# Sheet1.net
KiCad netlist of a schematic drawn in Altium Designer
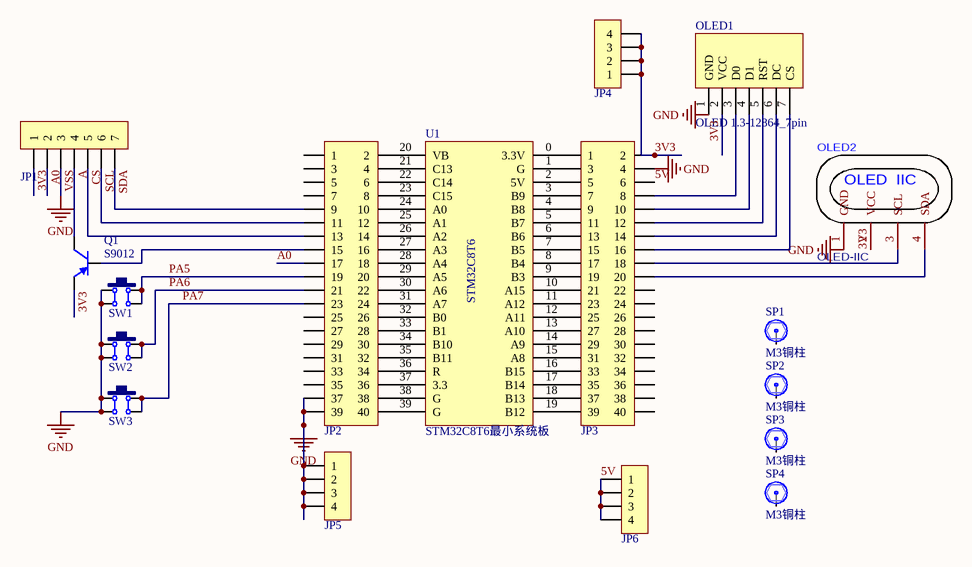
[diagram p0: Sheet1.SchDoc]

(export (version "E")
  (design (tool "Eeschema 10.0.6"))
  (components
    (comp (ref "JP1")
      (value "HDR-1X7")
      (footprint "XH2.54-WI-7P")
      (description "7P接插件  2.54")
      (fields (field (name "版权归属") "源创客"))
      (libsource (lib "MyLibra_Myself") (part "Header 7  2.54"))
    )
    (comp (ref "JP2")
      (value "Header 2X11")
      (footprint "HDR2.54-LI-2x20P")
      (description "20*2P接插件  2.54")
      (fields (field (name "版权归属") "源创客"))
      (libsource (lib "MyLibra_Myself") (part "Header 20X2  2.54"))
    )
    (comp (ref "JP3")
      (value "Header 2X11")
      (footprint "HDR2.54-LI-2x20P")
      (description "20*2P接插件  2.54")
      (fields (field (name "版权归属") "源创客"))
      (libsource (lib "MyLibra_Myself") (part "Header 20X2  2.54"))
    )
    (comp (ref "JP4")
      (value "HDR-1X4")
      (footprint "HDR2.54-M-LI-4P")
      (description "4P接插件  2.54")
      (fields (field (name "版权归属") "源创客"))
      (libsource (lib "") (part "Header 4  2.54_1"))
    )
    (comp (ref "JP5")
      (value "HDR-1X4")
      (footprint "HDR2.54-LI-4P")
      (description "4P接插件  2.54")
      (fields (field (name "版权归属") "源创客"))
      (libsource (lib "MyLibra_Myself") (part "Header 4  2.54"))
    )
    (comp (ref "JP6")
      (value "HDR-1X4")
      (footprint "HDR2.54-LI-4P")
      (description "4P接插件  2.54")
      (fields (field (name "版权归属") "源创客"))
      (libsource (lib "MyLibra_Myself") (part "Header 4  2.54"))
    )
    (comp (ref "OLED1")
      (value "OLED 1.3-12864_7pin")
      (footprint "1.3-SPI-OLED")
      (description "12864 点阵屏")
      (fields (field (name "版权归属") "源创客"))
      (libsource (lib "MyLibra_Myself") (part "OLED-SPI"))
    )
    (comp (ref "OLED2")
      (value "OLED-IIC")
      (footprint "0.96-IIC-OLED")
      (description "OLED 0.96寸 1.3寸 IIC显示屏")
      (libsource (lib "MyLibra_Myself") (part "OLED-IIC"))
    )
    (comp (ref "Q1")
      (value "S9012")
      (footprint "TO92A")
      (description "低频放大-PNP型")
      (fields (field (name "版权归属") "源创客"))
      (libsource (lib "综合库") (part "9012-DIP"))
    )
    (comp (ref "SP1")
      (value "M3铜柱")
      (footprint "M3x4_L")
      (description "铜柱")
      (fields (field (name "版权归属") "源创客"))
      (libsource (lib "综合库") (part "铜柱小焊盘"))
    )
    (comp (ref "SP2")
      (value "M3铜柱")
      (footprint "M3x4_L")
      (description "铜柱")
      (fields (field (name "版权归属") "源创客"))
      (libsource (lib "综合库") (part "铜柱小焊盘"))
    )
    (comp (ref "SP3")
      (value "M3铜柱")
      (footprint "M3x4_L")
      (description "铜柱")
      (fields (field (name "版权归属") "源创客"))
      (libsource (lib "综合库") (part "铜柱小焊盘"))
    )
    (comp (ref "SP4")
      (value "M3铜柱")
      (footprint "M3x4_L")
      (description "铜柱")
      (fields (field (name "版权归属") "源创客"))
      (libsource (lib "综合库") (part "铜柱小焊盘"))
    )
    (comp (ref "SW1")
      (value "12x12x5")
      (footprint "TSW DIP-12*12*4.3")
      (description "直插12x12轻触开关")
      (fields (field (name "版权归属") "源创客"))
      (libsource (lib "MyLibra_Myself") (part "TSW DIP-12x12"))
    )
    (comp (ref "SW2")
      (value "12x12x5")
      (footprint "TSW DIP-12*12*4.3")
      (description "直插12x12轻触开关")
      (fields (field (name "版权归属") "源创客"))
      (libsource (lib "MyLibra_Myself") (part "TSW DIP-12x12"))
    )
    (comp (ref "SW3")
      (value "12x12x5")
      (footprint "TSW DIP-12*12*4.3")
      (description "直插12x12轻触开关")
      (fields (field (name "版权归属") "源创客"))
      (libsource (lib "MyLibra_Myself") (part "TSW DIP-12x12"))
    )
    (comp (ref "U1")
      (value "STM32C8T6最小系统板")
      (footprint "STM32C8T6")
      (libsource (lib "MyLibra_Myself") (part "STM32C8T6最小系统板"))
    )
  )
  (nets
    (net (code "1") (name "/3V3") (class "Default")
      (node (ref "JP1") (pin "1") (pinfunction "1_1") (pintype "passive"))
      (node (ref "JP3") (pin "2") (pinfunction "2_2") (pintype "passive"))
      (node (ref "JP4") (pin "1") (pinfunction "1_1") (pintype "passive"))
      (node (ref "JP4") (pin "2") (pinfunction "2_2") (pintype "passive"))
      (node (ref "JP4") (pin "3") (pinfunction "3_3") (pintype "passive"))
      (node (ref "JP4") (pin "4") (pinfunction "4_4") (pintype "passive"))
      (node (ref "OLED1") (pin "2") (pinfunction "VCC_2") (pintype "passive"))
      (node (ref "OLED2") (pin "2") (pinfunction "VCC_2") (pintype "passive"))
      (node (ref "Q1") (pin "1") (pinfunction "E_1") (pintype "passive"))
    )
    (net (code "2") (name "/5V") (class "Default")
      (node (ref "JP3") (pin "6") (pinfunction "6_6") (pintype "passive"))
      (node (ref "JP6") (pin "1") (pinfunction "1_1") (pintype "passive"))
      (node (ref "JP6") (pin "2") (pinfunction "2_2") (pintype "passive"))
      (node (ref "JP6") (pin "3") (pinfunction "3_3") (pintype "passive"))
      (node (ref "JP6") (pin "4") (pinfunction "4_4") (pintype "passive"))
    )
    (net (code "3") (name "/A") (class "Default")
      (node (ref "JP1") (pin "4") (pinfunction "4_4") (pintype "passive"))
      (node (ref "Q1") (pin "3") (pinfunction "C_3") (pintype "passive"))
    )
    (net (code "4") (name "/A0") (class "Default")
      (node (ref "JP1") (pin "2") (pinfunction "2_2") (pintype "passive"))
      (node (ref "JP2") (pin "17") (pinfunction "17_17") (pintype "passive"))
    )
    (net (code "5") (name "/CS") (class "Default")
      (node (ref "JP1") (pin "5") (pinfunction "5_5") (pintype "passive"))
      (node (ref "JP2") (pin "13") (pinfunction "13_13") (pintype "passive"))
    )
    (net (code "6") (name "/PA5") (class "Default")
      (node (ref "JP2") (pin "19") (pinfunction "19_19") (pintype "passive"))
      (node (ref "SW1") (pin "2") (pinfunction "2_2") (pintype "passive"))
      (node (ref "SW1") (pin "3") (pinfunction "3_3") (pintype "passive"))
    )
    (net (code "7") (name "/PA6") (class "Default")
      (node (ref "JP2") (pin "21") (pinfunction "21_21") (pintype "passive"))
      (node (ref "SW2") (pin "2") (pinfunction "2_2") (pintype "passive"))
      (node (ref "SW2") (pin "3") (pinfunction "3_3") (pintype "passive"))
    )
    (net (code "8") (name "/PA7") (class "Default")
      (node (ref "JP2") (pin "23") (pinfunction "23_23") (pintype "passive"))
      (node (ref "SW3") (pin "2") (pinfunction "2_2") (pintype "passive"))
      (node (ref "SW3") (pin "3") (pinfunction "3_3") (pintype "passive"))
    )
    (net (code "9") (name "/SCL") (class "Default")
      (node (ref "JP1") (pin "6") (pinfunction "6_6") (pintype "passive"))
      (node (ref "JP2") (pin "11") (pinfunction "11_11") (pintype "passive"))
    )
    (net (code "10") (name "/SDA") (class "Default")
      (node (ref "JP1") (pin "7") (pinfunction "7_7") (pintype "passive"))
      (node (ref "JP2") (pin "9") (pinfunction "9_9") (pintype "passive"))
    )
    (net (code "11") (name "GND") (class "Default")
      (node (ref "JP1") (pin "3") (pinfunction "3_3") (pintype "passive"))
      (node (ref "JP2") (pin "37") (pinfunction "37_37") (pintype "passive"))
      (node (ref "JP2") (pin "39") (pinfunction "39_39") (pintype "passive"))
      (node (ref "JP3") (pin "4") (pinfunction "4_4") (pintype "passive"))
      (node (ref "JP5") (pin "1") (pinfunction "1_1") (pintype "passive"))
      (node (ref "JP5") (pin "2") (pinfunction "2_2") (pintype "passive"))
      (node (ref "JP5") (pin "3") (pinfunction "3_3") (pintype "passive"))
      (node (ref "JP5") (pin "4") (pinfunction "4_4") (pintype "passive"))
      (node (ref "OLED1") (pin "1") (pinfunction "GND_1") (pintype "passive"))
      (node (ref "OLED2") (pin "1") (pinfunction "GND_1") (pintype "passive"))
      (node (ref "SW1") (pin "1") (pinfunction "1_1") (pintype "passive"))
      (node (ref "SW1") (pin "4") (pinfunction "4_4") (pintype "passive"))
      (node (ref "SW2") (pin "1") (pinfunction "1_1") (pintype "passive"))
      (node (ref "SW2") (pin "4") (pinfunction "4_4") (pintype "passive"))
      (node (ref "SW3") (pin "1") (pinfunction "1_1") (pintype "passive"))
      (node (ref "SW3") (pin "4") (pinfunction "4_4") (pintype "passive"))
    )
    (net (code "12") (name "Net-(JP2-Pad38)") (class "Default")
      (node (ref "JP2") (pin "38") (pinfunction "38_38") (pintype "passive"))
      (node (ref "U1") (pin "38") (pinfunction "G_38") (pintype "passive"))
    )
    (net (code "13") (name "Net-(JP2-Pad40)") (class "Default")
      (node (ref "JP2") (pin "40") (pinfunction "40_40") (pintype "passive"))
      (node (ref "U1") (pin "39") (pinfunction "G_39") (pintype "passive"))
    )
    (net (code "14") (name "Net-(JP3-Pad3)") (class "Default")
      (node (ref "JP3") (pin "3") (pinfunction "3_3") (pintype "passive"))
      (node (ref "U1") (pin "1") (pinfunction "G_1") (pintype "passive"))
    )
    (net (code "15") (name "Net-(OLED1-CS)") (class "Default")
      (node (ref "JP3") (pin "16") (pinfunction "16_16") (pintype "passive"))
      (node (ref "OLED1") (pin "7") (pinfunction "CS_7") (pintype "passive"))
    )
    (net (code "16") (name "Net-(OLED1-D0)") (class "Default")
      (node (ref "JP3") (pin "8") (pinfunction "8_8") (pintype "passive"))
      (node (ref "OLED1") (pin "3") (pinfunction "D0_3") (pintype "passive"))
    )
    (net (code "17") (name "Net-(OLED1-D1)") (class "Default")
      (node (ref "JP3") (pin "10") (pinfunction "10_10") (pintype "passive"))
      (node (ref "OLED1") (pin "4") (pinfunction "D1_4") (pintype "passive"))
    )
    (net (code "18") (name "Net-(OLED1-DC)") (class "Default")
      (node (ref "JP3") (pin "14") (pinfunction "14_14") (pintype "passive"))
      (node (ref "OLED1") (pin "6") (pinfunction "DC_6") (pintype "passive"))
    )
    (net (code "19") (name "Net-(OLED1-RST)") (class "Default")
      (node (ref "JP3") (pin "12") (pinfunction "12_12") (pintype "passive"))
      (node (ref "OLED1") (pin "5") (pinfunction "RST_5") (pintype "passive"))
    )
    (net (code "20") (name "Net-(OLED2-SCL)") (class "Default")
      (node (ref "JP3") (pin "18") (pinfunction "18_18") (pintype "passive"))
      (node (ref "OLED2") (pin "3") (pinfunction "SCL_3") (pintype "passive"))
    )
    (net (code "21") (name "Net-(OLED2-SDA)") (class "Default")
      (node (ref "JP3") (pin "20") (pinfunction "20_20") (pintype "passive"))
      (node (ref "OLED2") (pin "4") (pinfunction "SDA_4") (pintype "passive"))
    )
    (net (code "22") (name "Net-(Q1-B)") (class "Default")
      (node (ref "JP2") (pin "15") (pinfunction "15_15") (pintype "passive"))
      (node (ref "Q1") (pin "2") (pinfunction "B_2") (pintype "passive"))
    )
    (net (code "23") (name "Net-(U1-3.3)") (class "Default")
      (node (ref "JP2") (pin "36") (pinfunction "36_36") (pintype "passive"))
      (node (ref "U1") (pin "37") (pinfunction "3.3_37") (pintype "passive"))
    )
    (net (code "24") (name "Net-(U1-3.3V)") (class "Default")
      (node (ref "JP3") (pin "1") (pinfunction "1_1") (pintype "passive"))
      (node (ref "U1") (pin "0") (pinfunction "3.3V_0") (pintype "passive"))
    )
    (net (code "25") (name "Net-(U1-5V)") (class "Default")
      (node (ref "JP3") (pin "5") (pinfunction "5_5") (pintype "passive"))
      (node (ref "U1") (pin "2") (pinfunction "5V_2") (pintype "passive"))
    )
    (net (code "26") (name "Net-(U1-A0)") (class "Default")
      (node (ref "JP2") (pin "10") (pinfunction "10_10") (pintype "passive"))
      (node (ref "U1") (pin "24") (pinfunction "A0_24") (pintype "passive"))
    )
    (net (code "27") (name "Net-(U1-A1)") (class "Default")
      (node (ref "JP2") (pin "12") (pinfunction "12_12") (pintype "passive"))
      (node (ref "U1") (pin "25") (pinfunction "A1_25") (pintype "passive"))
    )
    (net (code "28") (name "Net-(U1-A2)") (class "Default")
      (node (ref "JP2") (pin "14") (pinfunction "14_14") (pintype "passive"))
      (node (ref "U1") (pin "26") (pinfunction "A2_26") (pintype "passive"))
    )
    (net (code "29") (name "Net-(U1-A3)") (class "Default")
      (node (ref "JP2") (pin "16") (pinfunction "16_16") (pintype "passive"))
      (node (ref "U1") (pin "27") (pinfunction "A3_27") (pintype "passive"))
    )
    (net (code "30") (name "Net-(U1-A4)") (class "Default")
      (node (ref "JP2") (pin "18") (pinfunction "18_18") (pintype "passive"))
      (node (ref "U1") (pin "28") (pinfunction "A4_28") (pintype "passive"))
    )
    (net (code "31") (name "Net-(U1-A5)") (class "Default")
      (node (ref "JP2") (pin "20") (pinfunction "20_20") (pintype "passive"))
      (node (ref "U1") (pin "29") (pinfunction "A5_29") (pintype "passive"))
    )
    (net (code "32") (name "Net-(U1-A6)") (class "Default")
      (node (ref "JP2") (pin "22") (pinfunction "22_22") (pintype "passive"))
      (node (ref "U1") (pin "30") (pinfunction "A6_30") (pintype "passive"))
    )
    (net (code "33") (name "Net-(U1-A7)") (class "Default")
      (node (ref "JP2") (pin "24") (pinfunction "24_24") (pintype "passive"))
      (node (ref "U1") (pin "31") (pinfunction "A7_31") (pintype "passive"))
    )
    (net (code "34") (name "Net-(U1-A8)") (class "Default")
      (node (ref "JP3") (pin "31") (pinfunction "31_31") (pintype "passive"))
      (node (ref "U1") (pin "15") (pinfunction "A8_15") (pintype "passive"))
    )
    (net (code "35") (name "Net-(U1-A9)") (class "Default")
      (node (ref "JP3") (pin "29") (pinfunction "29_29") (pintype "passive"))
      (node (ref "U1") (pin "14") (pinfunction "A9_14") (pintype "passive"))
    )
    (net (code "36") (name "Net-(U1-A10)") (class "Default")
      (node (ref "JP3") (pin "27") (pinfunction "27_27") (pintype "passive"))
      (node (ref "U1") (pin "13") (pinfunction "A10_13") (pintype "passive"))
    )
    (net (code "37") (name "Net-(U1-A11)") (class "Default")
      (node (ref "JP3") (pin "25") (pinfunction "25_25") (pintype "passive"))
      (node (ref "U1") (pin "12") (pinfunction "A11_12") (pintype "passive"))
    )
    (net (code "38") (name "Net-(U1-A12)") (class "Default")
      (node (ref "JP3") (pin "23") (pinfunction "23_23") (pintype "passive"))
      (node (ref "U1") (pin "11") (pinfunction "A12_11") (pintype "passive"))
    )
    (net (code "39") (name "Net-(U1-A15)") (class "Default")
      (node (ref "JP3") (pin "21") (pinfunction "21_21") (pintype "passive"))
      (node (ref "U1") (pin "10") (pinfunction "A15_10") (pintype "passive"))
    )
    (net (code "40") (name "Net-(U1-B0)") (class "Default")
      (node (ref "JP2") (pin "26") (pinfunction "26_26") (pintype "passive"))
      (node (ref "U1") (pin "32") (pinfunction "B0_32") (pintype "passive"))
    )
    (net (code "41") (name "Net-(U1-B1)") (class "Default")
      (node (ref "JP2") (pin "28") (pinfunction "28_28") (pintype "passive"))
      (node (ref "U1") (pin "33") (pinfunction "B1_33") (pintype "passive"))
    )
    (net (code "42") (name "Net-(U1-B3)") (class "Default")
      (node (ref "JP3") (pin "19") (pinfunction "19_19") (pintype "passive"))
      (node (ref "U1") (pin "9") (pinfunction "B3_9") (pintype "passive"))
    )
    (net (code "43") (name "Net-(U1-B4)") (class "Default")
      (node (ref "JP3") (pin "17") (pinfunction "17_17") (pintype "passive"))
      (node (ref "U1") (pin "8") (pinfunction "B4_8") (pintype "passive"))
    )
    (net (code "44") (name "Net-(U1-B5)") (class "Default")
      (node (ref "JP3") (pin "15") (pinfunction "15_15") (pintype "passive"))
      (node (ref "U1") (pin "7") (pinfunction "B5_7") (pintype "passive"))
    )
    (net (code "45") (name "Net-(U1-B6)") (class "Default")
      (node (ref "JP3") (pin "13") (pinfunction "13_13") (pintype "passive"))
      (node (ref "U1") (pin "6") (pinfunction "B6_6") (pintype "passive"))
    )
    (net (code "46") (name "Net-(U1-B7)") (class "Default")
      (node (ref "JP3") (pin "11") (pinfunction "11_11") (pintype "passive"))
      (node (ref "U1") (pin "5") (pinfunction "B7_5") (pintype "passive"))
    )
    (net (code "47") (name "Net-(U1-B8)") (class "Default")
      (node (ref "JP3") (pin "9") (pinfunction "9_9") (pintype "passive"))
      (node (ref "U1") (pin "4") (pinfunction "B8_4") (pintype "passive"))
    )
    (net (code "48") (name "Net-(U1-B9)") (class "Default")
      (node (ref "JP3") (pin "7") (pinfunction "7_7") (pintype "passive"))
      (node (ref "U1") (pin "3") (pinfunction "B9_3") (pintype "passive"))
    )
    (net (code "49") (name "Net-(U1-B10)") (class "Default")
      (node (ref "JP2") (pin "30") (pinfunction "30_30") (pintype "passive"))
      (node (ref "U1") (pin "34") (pinfunction "B10_34") (pintype "passive"))
    )
    (net (code "50") (name "Net-(U1-B11)") (class "Default")
      (node (ref "JP2") (pin "32") (pinfunction "32_32") (pintype "passive"))
      (node (ref "U1") (pin "35") (pinfunction "B11_35") (pintype "passive"))
    )
    (net (code "51") (name "Net-(U1-B12)") (class "Default")
      (node (ref "JP3") (pin "39") (pinfunction "39_39") (pintype "passive"))
      (node (ref "U1") (pin "19") (pinfunction "B12_19") (pintype "passive"))
    )
    (net (code "52") (name "Net-(U1-B13)") (class "Default")
      (node (ref "JP3") (pin "37") (pinfunction "37_37") (pintype "passive"))
      (node (ref "U1") (pin "18") (pinfunction "B13_18") (pintype "passive"))
    )
    (net (code "53") (name "Net-(U1-B14)") (class "Default")
      (node (ref "JP3") (pin "35") (pinfunction "35_35") (pintype "passive"))
      (node (ref "U1") (pin "17") (pinfunction "B14_17") (pintype "passive"))
    )
    (net (code "54") (name "Net-(U1-B15)") (class "Default")
      (node (ref "JP3") (pin "33") (pinfunction "33_33") (pintype "passive"))
      (node (ref "U1") (pin "16") (pinfunction "B15_16") (pintype "passive"))
    )
    (net (code "55") (name "Net-(U1-C13)") (class "Default")
      (node (ref "JP2") (pin "4") (pinfunction "4_4") (pintype "passive"))
      (node (ref "U1") (pin "21") (pinfunction "C13_21") (pintype "passive"))
    )
    (net (code "56") (name "Net-(U1-C14)") (class "Default")
      (node (ref "JP2") (pin "6") (pinfunction "6_6") (pintype "passive"))
      (node (ref "U1") (pin "22") (pinfunction "C14_22") (pintype "passive"))
    )
    (net (code "57") (name "Net-(U1-C15)") (class "Default")
      (node (ref "JP2") (pin "8") (pinfunction "8_8") (pintype "passive"))
      (node (ref "U1") (pin "23") (pinfunction "C15_23") (pintype "passive"))
    )
    (net (code "58") (name "Net-(U1-R)") (class "Default")
      (node (ref "JP2") (pin "34") (pinfunction "34_34") (pintype "passive"))
      (node (ref "U1") (pin "36") (pinfunction "R_36") (pintype "passive"))
    )
    (net (code "59") (name "Net-(U1-VB)") (class "Default")
      (node (ref "JP2") (pin "2") (pinfunction "2_2") (pintype "passive"))
      (node (ref "U1") (pin "20") (pinfunction "VB_20") (pintype "passive"))
    )
    (net (code "60") (name "unconnected-(JP2-Pad1)") (class "Default")
      (node (ref "JP2") (pin "1") (pinfunction "1_1") (pintype "passive"))
    )
    (net (code "61") (name "unconnected-(JP2-Pad3)") (class "Default")
      (node (ref "JP2") (pin "3") (pinfunction "3_3") (pintype "passive"))
    )
    (net (code "62") (name "unconnected-(JP2-Pad5)") (class "Default")
      (node (ref "JP2") (pin "5") (pinfunction "5_5") (pintype "passive"))
    )
    (net (code "63") (name "unconnected-(JP2-Pad7)") (class "Default")
      (node (ref "JP2") (pin "7") (pinfunction "7_7") (pintype "passive"))
    )
    (net (code "64") (name "unconnected-(JP2-Pad25)") (class "Default")
      (node (ref "JP2") (pin "25") (pinfunction "25_25") (pintype "passive"))
    )
    (net (code "65") (name "unconnected-(JP2-Pad27)") (class "Default")
      (node (ref "JP2") (pin "27") (pinfunction "27_27") (pintype "passive"))
    )
    (net (code "66") (name "unconnected-(JP2-Pad29)") (class "Default")
      (node (ref "JP2") (pin "29") (pinfunction "29_29") (pintype "passive"))
    )
    (net (code "67") (name "unconnected-(JP2-Pad31)") (class "Default")
      (node (ref "JP2") (pin "31") (pinfunction "31_31") (pintype "passive"))
    )
    (net (code "68") (name "unconnected-(JP2-Pad33)") (class "Default")
      (node (ref "JP2") (pin "33") (pinfunction "33_33") (pintype "passive"))
    )
    (net (code "69") (name "unconnected-(JP2-Pad35)") (class "Default")
      (node (ref "JP2") (pin "35") (pinfunction "35_35") (pintype "passive"))
    )
    (net (code "70") (name "unconnected-(JP3-Pad22)") (class "Default")
      (node (ref "JP3") (pin "22") (pinfunction "22_22") (pintype "passive"))
    )
    (net (code "71") (name "unconnected-(JP3-Pad24)") (class "Default")
      (node (ref "JP3") (pin "24") (pinfunction "24_24") (pintype "passive"))
    )
    (net (code "72") (name "unconnected-(JP3-Pad26)") (class "Default")
      (node (ref "JP3") (pin "26") (pinfunction "26_26") (pintype "passive"))
    )
    (net (code "73") (name "unconnected-(JP3-Pad28)") (class "Default")
      (node (ref "JP3") (pin "28") (pinfunction "28_28") (pintype "passive"))
    )
    (net (code "74") (name "unconnected-(JP3-Pad30)") (class "Default")
      (node (ref "JP3") (pin "30") (pinfunction "30_30") (pintype "passive"))
    )
    (net (code "75") (name "unconnected-(JP3-Pad32)") (class "Default")
      (node (ref "JP3") (pin "32") (pinfunction "32_32") (pintype "passive"))
    )
    (net (code "76") (name "unconnected-(JP3-Pad34)") (class "Default")
      (node (ref "JP3") (pin "34") (pinfunction "34_34") (pintype "passive"))
    )
    (net (code "77") (name "unconnected-(JP3-Pad36)") (class "Default")
      (node (ref "JP3") (pin "36") (pinfunction "36_36") (pintype "passive"))
    )
    (net (code "78") (name "unconnected-(JP3-Pad38)") (class "Default")
      (node (ref "JP3") (pin "38") (pinfunction "38_38") (pintype "passive"))
    )
    (net (code "79") (name "unconnected-(JP3-Pad40)") (class "Default")
      (node (ref "JP3") (pin "40") (pinfunction "40_40") (pintype "passive"))
    )
    (net (code "80") (name "unconnected-(SP1-Pad1)") (class "Default")
      (node (ref "SP1") (pin "1") (pinfunction "1_1") (pintype "passive"))
    )
    (net (code "81") (name "unconnected-(SP2-Pad1)") (class "Default")
      (node (ref "SP2") (pin "1") (pinfunction "1_1") (pintype "passive"))
    )
    (net (code "82") (name "unconnected-(SP3-Pad1)") (class "Default")
      (node (ref "SP3") (pin "1") (pinfunction "1_1") (pintype "passive"))
    )
    (net (code "83") (name "unconnected-(SP4-Pad1)") (class "Default")
      (node (ref "SP4") (pin "1") (pinfunction "1_1") (pintype "passive"))
    )
  )
)
